# connectors.net
KiCad netlist of a schematic drawn in Altium Designer
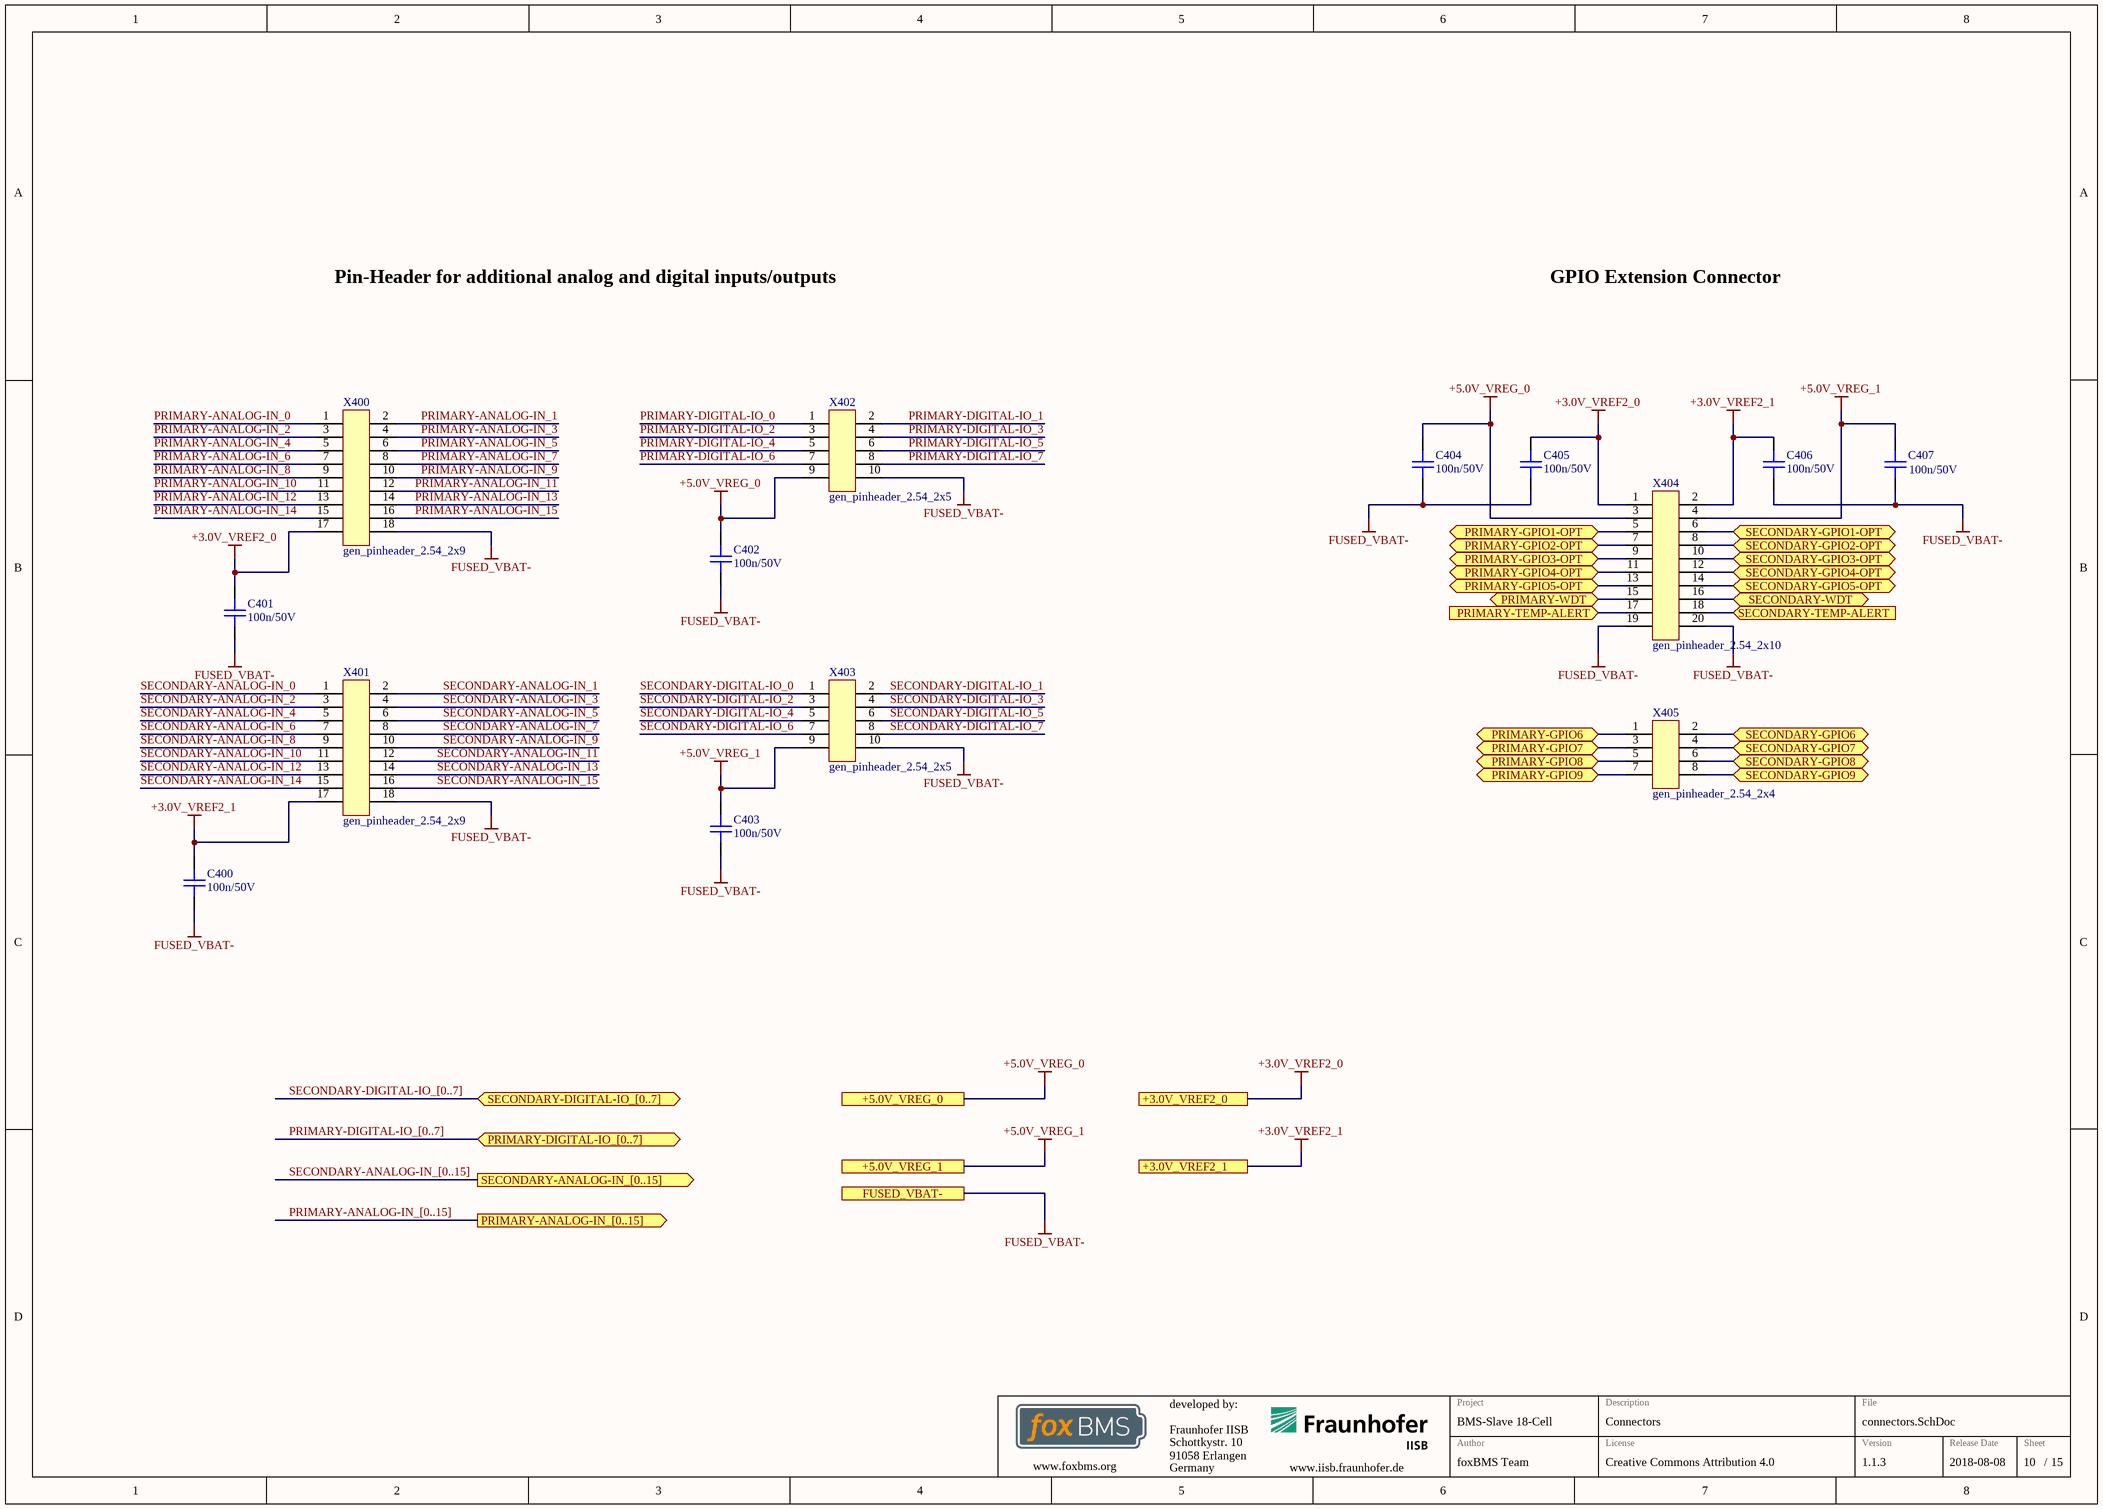
[diagram p0: connectors.SchDoc]

(export (version "E")
  (design (tool "Eeschema 10.0.6"))
  (components
    (comp (ref "C400")
      (value "100n/50V")
      (footprint "CAPC1608X08N")
      (description "MLCC")
      (fields (field (name "PART NUMBER") "gen_C_ceramic_100n_50V_X7R_0603"))
      (libsource (lib "OE750") (part "C"))
    )
    (comp (ref "C401")
      (value "100n/50V")
      (footprint "CAPC1608X08N")
      (description "MLCC")
      (fields (field (name "PART NUMBER") "gen_C_ceramic_100n_50V_X7R_0603"))
      (libsource (lib "OE750") (part "C"))
    )
    (comp (ref "C402")
      (value "100n/50V")
      (footprint "CAPC1608X08N")
      (description "MLCC")
      (fields (field (name "PART NUMBER") "gen_C_ceramic_100n_50V_X7R_0603"))
      (libsource (lib "OE750") (part "C"))
    )
    (comp (ref "C403")
      (value "100n/50V")
      (footprint "CAPC1608X08N")
      (description "MLCC")
      (fields (field (name "PART NUMBER") "gen_C_ceramic_100n_50V_X7R_0603"))
      (libsource (lib "OE750") (part "C"))
    )
    (comp (ref "C404")
      (value "100n/50V")
      (footprint "CAPC1608X08N")
      (description "MLCC")
      (fields (field (name "PART NUMBER") "gen_C_ceramic_100n_50V_X7R_0603"))
      (libsource (lib "OE750") (part "C"))
    )
    (comp (ref "C405")
      (value "100n/50V")
      (footprint "CAPC1608X08N")
      (description "MLCC")
      (fields (field (name "PART NUMBER") "gen_C_ceramic_100n_50V_X7R_0603"))
      (libsource (lib "OE750") (part "C"))
    )
    (comp (ref "C406")
      (value "100n/50V")
      (footprint "CAPC1608X08N")
      (description "MLCC")
      (fields (field (name "PART NUMBER") "gen_C_ceramic_100n_50V_X7R_0603"))
      (libsource (lib "OE750") (part "C"))
    )
    (comp (ref "C407")
      (value "100n/50V")
      (footprint "CAPC1608X08N")
      (description "MLCC")
      (fields (field (name "PART NUMBER") "gen_C_ceramic_100n_50V_X7R_0603"))
      (libsource (lib "OE750") (part "C"))
    )
    (comp (ref "X400")
      (value "gen_pinheader_2.54_2x9")
      (footprint "Pinheader_2.54_2x9")
      (description "Standard Pinheader, THD, gerade, 2.54mm, 2-reihig")
      (libsource (lib "OE750") (part "X2x9"))
    )
    (comp (ref "X401")
      (value "gen_pinheader_2.54_2x9")
      (footprint "Pinheader_2.54_2x9")
      (description "Standard Pinheader, THD, gerade, 2.54mm, 2-reihig")
      (libsource (lib "OE750") (part "X2x9"))
    )
    (comp (ref "X402")
      (value "gen_pinheader_2.54_2x5")
      (footprint "Pinheader_2.54_2x5")
      (description "Standard Pinheader, THD, gerade, 2.54mm, 2-reihig")
      (libsource (lib "OE750") (part "X2x5"))
    )
    (comp (ref "X403")
      (value "gen_pinheader_2.54_2x5")
      (footprint "Pinheader_2.54_2x5")
      (description "Standard Pinheader, THD, gerade, 2.54mm, 2-reihig")
      (libsource (lib "OE750") (part "X2x5"))
    )
    (comp (ref "X404")
      (value "gen_pinheader_2.54_2x10")
      (footprint "Pinheader_2.54_2x10")
      (description "Standard Pinheader, THD, gerade, 2.54mm, 2-reihig")
      (libsource (lib "OE750") (part "X2x10"))
    )
    (comp (ref "X405")
      (value "gen_pinheader_2.54_2x4")
      (footprint "Pinheader_2.54_2x4")
      (description "Standard Pinheader, THD, gerade, 2.54mm, 2-reihig")
      (libsource (lib "OE750") (part "X2x4"))
    )
  )
  (nets
    (net (code "1") (name "+3.0V_VREF2_0") (class "Default")
      (node (ref "C401") (pin "2") (pinfunction "2_2") (pintype "passive"))
      (node (ref "C405") (pin "2") (pinfunction "2_2") (pintype "passive"))
      (node (ref "X400") (pin "17") (pintype "passive"))
      (node (ref "X404") (pin "1") (pintype "passive"))
    )
    (net (code "2") (name "+3.0V_VREF2_1") (class "Default")
      (node (ref "C400") (pin "2") (pinfunction "2_2") (pintype "passive"))
      (node (ref "C406") (pin "2") (pinfunction "2_2") (pintype "passive"))
      (node (ref "X401") (pin "17") (pintype "passive"))
      (node (ref "X404") (pin "2") (pintype "passive"))
    )
    (net (code "3") (name "+5.0V_VREG_0") (class "Default")
      (node (ref "C402") (pin "2") (pinfunction "2_2") (pintype "passive"))
      (node (ref "C404") (pin "2") (pinfunction "2_2") (pintype "passive"))
      (node (ref "X402") (pin "9") (pintype "passive"))
      (node (ref "X404") (pin "3") (pintype "passive"))
    )
    (net (code "4") (name "+5.0V_VREG_1") (class "Default")
      (node (ref "C403") (pin "2") (pinfunction "2_2") (pintype "passive"))
      (node (ref "C407") (pin "2") (pinfunction "2_2") (pintype "passive"))
      (node (ref "X403") (pin "9") (pintype "passive"))
      (node (ref "X404") (pin "4") (pintype "passive"))
    )
    (net (code "5") (name "/PRIMARY-ANALOG-IN_0") (class "Default")
      (node (ref "X400") (pin "1") (pintype "passive"))
    )
    (net (code "6") (name "/PRIMARY-ANALOG-IN_1") (class "Default")
      (node (ref "X400") (pin "2") (pintype "passive"))
    )
    (net (code "7") (name "/PRIMARY-ANALOG-IN_2") (class "Default")
      (node (ref "X400") (pin "3") (pintype "passive"))
    )
    (net (code "8") (name "/PRIMARY-ANALOG-IN_3") (class "Default")
      (node (ref "X400") (pin "4") (pintype "passive"))
    )
    (net (code "9") (name "/PRIMARY-ANALOG-IN_4") (class "Default")
      (node (ref "X400") (pin "5") (pintype "passive"))
    )
    (net (code "10") (name "/PRIMARY-ANALOG-IN_5") (class "Default")
      (node (ref "X400") (pin "6") (pintype "passive"))
    )
    (net (code "11") (name "/PRIMARY-ANALOG-IN_6") (class "Default")
      (node (ref "X400") (pin "7") (pintype "passive"))
    )
    (net (code "12") (name "/PRIMARY-ANALOG-IN_7") (class "Default")
      (node (ref "X400") (pin "8") (pintype "passive"))
    )
    (net (code "13") (name "/PRIMARY-ANALOG-IN_8") (class "Default")
      (node (ref "X400") (pin "9") (pintype "passive"))
    )
    (net (code "14") (name "/PRIMARY-ANALOG-IN_9") (class "Default")
      (node (ref "X400") (pin "10") (pintype "passive"))
    )
    (net (code "15") (name "/PRIMARY-ANALOG-IN_10") (class "Default")
      (node (ref "X400") (pin "11") (pintype "passive"))
    )
    (net (code "16") (name "/PRIMARY-ANALOG-IN_11") (class "Default")
      (node (ref "X400") (pin "12") (pintype "passive"))
    )
    (net (code "17") (name "/PRIMARY-ANALOG-IN_12") (class "Default")
      (node (ref "X400") (pin "13") (pintype "passive"))
    )
    (net (code "18") (name "/PRIMARY-ANALOG-IN_13") (class "Default")
      (node (ref "X400") (pin "14") (pintype "passive"))
    )
    (net (code "19") (name "/PRIMARY-ANALOG-IN_14") (class "Default")
      (node (ref "X400") (pin "15") (pintype "passive"))
    )
    (net (code "20") (name "/PRIMARY-ANALOG-IN_15") (class "Default")
      (node (ref "X400") (pin "16") (pintype "passive"))
    )
    (net (code "22") (name "/PRIMARY-DIGITAL-IO_0") (class "Default")
      (node (ref "X402") (pin "1") (pintype "passive"))
    )
    (net (code "23") (name "/PRIMARY-DIGITAL-IO_1") (class "Default")
      (node (ref "X402") (pin "2") (pintype "passive"))
    )
    (net (code "24") (name "/PRIMARY-DIGITAL-IO_2") (class "Default")
      (node (ref "X402") (pin "3") (pintype "passive"))
    )
    (net (code "25") (name "/PRIMARY-DIGITAL-IO_3") (class "Default")
      (node (ref "X402") (pin "4") (pintype "passive"))
    )
    (net (code "26") (name "/PRIMARY-DIGITAL-IO_4") (class "Default")
      (node (ref "X402") (pin "5") (pintype "passive"))
    )
    (net (code "27") (name "/PRIMARY-DIGITAL-IO_5") (class "Default")
      (node (ref "X402") (pin "6") (pintype "passive"))
    )
    (net (code "28") (name "/PRIMARY-DIGITAL-IO_6") (class "Default")
      (node (ref "X402") (pin "7") (pintype "passive"))
    )
    (net (code "29") (name "/PRIMARY-DIGITAL-IO_7") (class "Default")
      (node (ref "X402") (pin "8") (pintype "passive"))
    )
    (net (code "31") (name "/PRIMARY-GPIO1-OPT") (class "Default")
      (node (ref "X404") (pin "5") (pintype "passive"))
    )
    (net (code "32") (name "/PRIMARY-GPIO2-OPT") (class "Default")
      (node (ref "X404") (pin "7") (pintype "passive"))
    )
    (net (code "33") (name "/PRIMARY-GPIO3-OPT") (class "Default")
      (node (ref "X404") (pin "9") (pintype "passive"))
    )
    (net (code "34") (name "/PRIMARY-GPIO4-OPT") (class "Default")
      (node (ref "X404") (pin "11") (pintype "passive"))
    )
    (net (code "35") (name "/PRIMARY-GPIO5-OPT") (class "Default")
      (node (ref "X404") (pin "13") (pintype "passive"))
    )
    (net (code "36") (name "/PRIMARY-GPIO6") (class "Default")
      (node (ref "X405") (pin "1") (pintype "passive"))
    )
    (net (code "37") (name "/PRIMARY-GPIO7") (class "Default")
      (node (ref "X405") (pin "3") (pintype "passive"))
    )
    (net (code "38") (name "/PRIMARY-GPIO8") (class "Default")
      (node (ref "X405") (pin "5") (pintype "passive"))
    )
    (net (code "39") (name "/PRIMARY-GPIO9") (class "Default")
      (node (ref "X405") (pin "7") (pintype "passive"))
    )
    (net (code "40") (name "/PRIMARY-TEMP-ALERT") (class "Default")
      (node (ref "X404") (pin "17") (pintype "passive"))
    )
    (net (code "41") (name "/PRIMARY-WDT") (class "Default")
      (node (ref "X404") (pin "15") (pintype "passive"))
    )
    (net (code "42") (name "/SECONDARY-ANALOG-IN_0") (class "Default")
      (node (ref "X401") (pin "1") (pintype "passive"))
    )
    (net (code "43") (name "/SECONDARY-ANALOG-IN_1") (class "Default")
      (node (ref "X401") (pin "2") (pintype "passive"))
    )
    (net (code "44") (name "/SECONDARY-ANALOG-IN_2") (class "Default")
      (node (ref "X401") (pin "3") (pintype "passive"))
    )
    (net (code "45") (name "/SECONDARY-ANALOG-IN_3") (class "Default")
      (node (ref "X401") (pin "4") (pintype "passive"))
    )
    (net (code "46") (name "/SECONDARY-ANALOG-IN_4") (class "Default")
      (node (ref "X401") (pin "5") (pintype "passive"))
    )
    (net (code "47") (name "/SECONDARY-ANALOG-IN_5") (class "Default")
      (node (ref "X401") (pin "6") (pintype "passive"))
    )
    (net (code "48") (name "/SECONDARY-ANALOG-IN_6") (class "Default")
      (node (ref "X401") (pin "7") (pintype "passive"))
    )
    (net (code "49") (name "/SECONDARY-ANALOG-IN_7") (class "Default")
      (node (ref "X401") (pin "8") (pintype "passive"))
    )
    (net (code "50") (name "/SECONDARY-ANALOG-IN_8") (class "Default")
      (node (ref "X401") (pin "9") (pintype "passive"))
    )
    (net (code "51") (name "/SECONDARY-ANALOG-IN_9") (class "Default")
      (node (ref "X401") (pin "10") (pintype "passive"))
    )
    (net (code "52") (name "/SECONDARY-ANALOG-IN_10") (class "Default")
      (node (ref "X401") (pin "11") (pintype "passive"))
    )
    (net (code "53") (name "/SECONDARY-ANALOG-IN_11") (class "Default")
      (node (ref "X401") (pin "12") (pintype "passive"))
    )
    (net (code "54") (name "/SECONDARY-ANALOG-IN_12") (class "Default")
      (node (ref "X401") (pin "13") (pintype "passive"))
    )
    (net (code "55") (name "/SECONDARY-ANALOG-IN_13") (class "Default")
      (node (ref "X401") (pin "14") (pintype "passive"))
    )
    (net (code "56") (name "/SECONDARY-ANALOG-IN_14") (class "Default")
      (node (ref "X401") (pin "15") (pintype "passive"))
    )
    (net (code "57") (name "/SECONDARY-ANALOG-IN_15") (class "Default")
      (node (ref "X401") (pin "16") (pintype "passive"))
    )
    (net (code "59") (name "/SECONDARY-DIGITAL-IO_0") (class "Default")
      (node (ref "X403") (pin "1") (pintype "passive"))
    )
    (net (code "60") (name "/SECONDARY-DIGITAL-IO_1") (class "Default")
      (node (ref "X403") (pin "2") (pintype "passive"))
    )
    (net (code "61") (name "/SECONDARY-DIGITAL-IO_2") (class "Default")
      (node (ref "X403") (pin "3") (pintype "passive"))
    )
    (net (code "62") (name "/SECONDARY-DIGITAL-IO_3") (class "Default")
      (node (ref "X403") (pin "4") (pintype "passive"))
    )
    (net (code "63") (name "/SECONDARY-DIGITAL-IO_4") (class "Default")
      (node (ref "X403") (pin "5") (pintype "passive"))
    )
    (net (code "64") (name "/SECONDARY-DIGITAL-IO_5") (class "Default")
      (node (ref "X403") (pin "6") (pintype "passive"))
    )
    (net (code "65") (name "/SECONDARY-DIGITAL-IO_6") (class "Default")
      (node (ref "X403") (pin "7") (pintype "passive"))
    )
    (net (code "66") (name "/SECONDARY-DIGITAL-IO_7") (class "Default")
      (node (ref "X403") (pin "8") (pintype "passive"))
    )
    (net (code "68") (name "/SECONDARY-GPIO1-OPT") (class "Default")
      (node (ref "X404") (pin "6") (pintype "passive"))
    )
    (net (code "69") (name "/SECONDARY-GPIO2-OPT") (class "Default")
      (node (ref "X404") (pin "8") (pintype "passive"))
    )
    (net (code "70") (name "/SECONDARY-GPIO3-OPT") (class "Default")
      (node (ref "X404") (pin "10") (pintype "passive"))
    )
    (net (code "71") (name "/SECONDARY-GPIO4-OPT") (class "Default")
      (node (ref "X404") (pin "12") (pintype "passive"))
    )
    (net (code "72") (name "/SECONDARY-GPIO5-OPT") (class "Default")
      (node (ref "X404") (pin "14") (pintype "passive"))
    )
    (net (code "73") (name "/SECONDARY-GPIO6") (class "Default")
      (node (ref "X405") (pin "2") (pintype "passive"))
    )
    (net (code "74") (name "/SECONDARY-GPIO7") (class "Default")
      (node (ref "X405") (pin "4") (pintype "passive"))
    )
    (net (code "75") (name "/SECONDARY-GPIO8") (class "Default")
      (node (ref "X405") (pin "6") (pintype "passive"))
    )
    (net (code "76") (name "/SECONDARY-GPIO9") (class "Default")
      (node (ref "X405") (pin "8") (pintype "passive"))
    )
    (net (code "77") (name "/SECONDARY-TEMP-ALERT") (class "Default")
      (node (ref "X404") (pin "18") (pintype "passive"))
    )
    (net (code "78") (name "/SECONDARY-WDT") (class "Default")
      (node (ref "X404") (pin "16") (pintype "passive"))
    )
    (net (code "79") (name "FUSED_VBAT-") (class "Default")
      (node (ref "C400") (pin "1") (pinfunction "1_1") (pintype "passive"))
      (node (ref "C401") (pin "1") (pinfunction "1_1") (pintype "passive"))
      (node (ref "C402") (pin "1") (pinfunction "1_1") (pintype "passive"))
      (node (ref "C403") (pin "1") (pinfunction "1_1") (pintype "passive"))
      (node (ref "C404") (pin "1") (pinfunction "1_1") (pintype "passive"))
      (node (ref "C405") (pin "1") (pinfunction "1_1") (pintype "passive"))
      (node (ref "C406") (pin "1") (pinfunction "1_1") (pintype "passive"))
      (node (ref "C407") (pin "1") (pinfunction "1_1") (pintype "passive"))
      (node (ref "X400") (pin "18") (pintype "passive"))
      (node (ref "X401") (pin "18") (pintype "passive"))
      (node (ref "X402") (pin "10") (pintype "passive"))
      (node (ref "X403") (pin "10") (pintype "passive"))
      (node (ref "X404") (pin "19") (pintype "passive"))
      (node (ref "X404") (pin "20") (pintype "passive"))
    )
  )
)
